# THAT_1646_Breakout.net
KiCad netlist of a schematic drawn in EAGLE
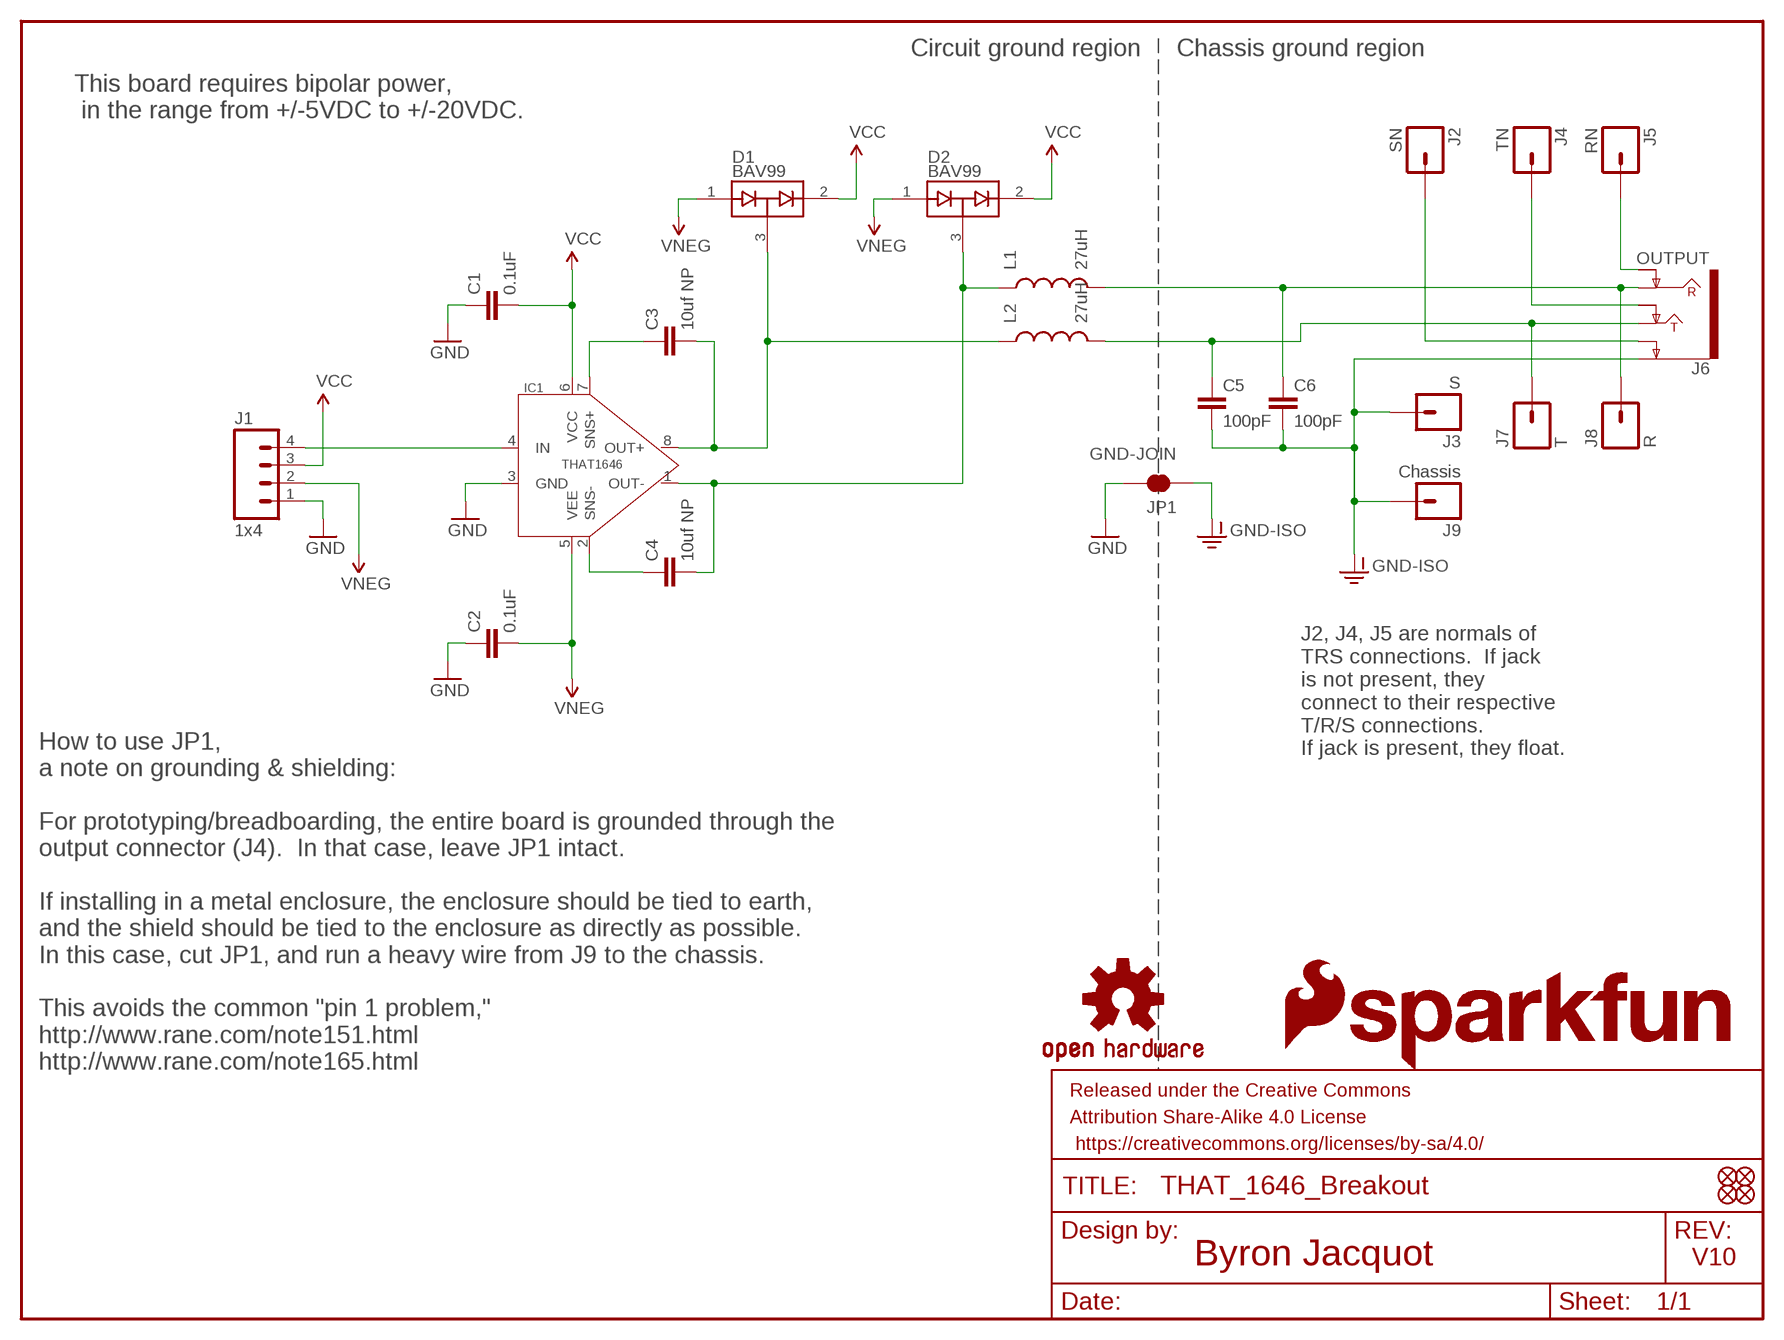
[diagram p0: schematic, sheet 1]

(export (version "E")
  (design (tool "Eeschema 10.0.6"))
  (components
    (comp (ref "C1")
      (value "0.1uF")
      (footprint "eagle-import:0603-CAP")
      (libsource (lib "eagle-import") (part "0.1UF-25V-5%(0603)"))
    )
    (comp (ref "C2")
      (value "0.1uF")
      (footprint "eagle-import:0603-CAP")
      (libsource (lib "eagle-import") (part "0.1UF-25V-5%(0603)"))
    )
    (comp (ref "C3")
      (value "10uf NP")
      (footprint "eagle-import:PANASONIC_D")
      (fields (field (name "MFR") "Panasonic"))
      (libsource (lib "eagle-import") (part "PANA-EEE-1EA100NP"))
    )
    (comp (ref "C4")
      (value "10uf NP")
      (footprint "eagle-import:PANASONIC_D")
      (fields (field (name "MFR") "Panasonic"))
      (libsource (lib "eagle-import") (part "PANA-EEE-1EA100NP"))
    )
    (comp (ref "C5")
      (value "100pF")
      (footprint "eagle-import:0603-CAP")
      (libsource (lib "eagle-import") (part "100PF-50V-5%(0603)"))
    )
    (comp (ref "C6")
      (value "100pF")
      (footprint "eagle-import:0603-CAP")
      (libsource (lib "eagle-import") (part "100PF-50V-5%(0603)"))
    )
    (comp (ref "D1")
      (value "BAV99")
      (footprint "eagle-import:SOT23-3")
      (libsource (lib "eagle-import") (part "BAV99"))
    )
    (comp (ref "D2")
      (value "BAV99")
      (footprint "eagle-import:SOT23-3")
      (libsource (lib "eagle-import") (part "BAV99"))
    )
    (comp (ref "FD1")
      (value "FIDUCIALUFIDUCIAL")
      (footprint "eagle-import:MICRO-FIDUCIAL")
      (libsource (lib "eagle-import") (part "FIDUCIALUFIDUCIAL"))
    )
    (comp (ref "FD2")
      (value "FIDUCIALUFIDUCIAL")
      (footprint "eagle-import:MICRO-FIDUCIAL")
      (libsource (lib "eagle-import") (part "FIDUCIALUFIDUCIAL"))
    )
    (comp (ref "FD3")
      (value "FIDUCIALUFIDUCIAL")
      (footprint "eagle-import:MICRO-FIDUCIAL")
      (libsource (lib "eagle-import") (part "FIDUCIALUFIDUCIAL"))
    )
    (comp (ref "FD4")
      (value "FIDUCIALUFIDUCIAL")
      (footprint "eagle-import:MICRO-FIDUCIAL")
      (libsource (lib "eagle-import") (part "FIDUCIALUFIDUCIAL"))
    )
    (comp (ref "FRAME1")
      (value "FRAME-LETTER")
      (footprint "eagle-import:CREATIVE_COMMONS")
      (libsource (lib "eagle-import") (part "FRAME-LETTER"))
    )
    (comp (ref "IC1")
      (value "THAT1646")
      (footprint "eagle-import:SO08")
      (libsource (lib "eagle-import") (part "THAT1646"))
    )
    (comp (ref "J1")
      (value "1x4")
      (footprint "eagle-import:1X04_NO_SILK_ALL_ROUND")
      (libsource (lib "eagle-import") (part "M04NO_SILK_ALL_ROUND"))
    )
    (comp (ref "J2")
      (value "SN")
      (footprint "eagle-import:1X01_NO_SILK")
      (libsource (lib "eagle-import") (part "M01PTH_NO_SILK_YES_STOP"))
    )
    (comp (ref "J3")
      (value "S")
      (footprint "eagle-import:1X01_NO_SILK")
      (libsource (lib "eagle-import") (part "M01PTH_NO_SILK_YES_STOP"))
    )
    (comp (ref "J4")
      (value "TN")
      (footprint "eagle-import:1X01_NO_SILK")
      (libsource (lib "eagle-import") (part "M01PTH_NO_SILK_YES_STOP"))
    )
    (comp (ref "J5")
      (value "RN")
      (footprint "eagle-import:1X01_NO_SILK")
      (libsource (lib "eagle-import") (part "M01PTH_NO_SILK_YES_STOP"))
    )
    (comp (ref "J6")
      (value "OUTPUT")
      (footprint "eagle-import:AUDIO_JACK_0.25__TRS_PTH_RA")
      (libsource (lib "eagle-import") (part "AUDIO_JACK_TRS_0.25{dblquote}_PTH_RA"))
    )
    (comp (ref "J7")
      (value "T")
      (footprint "eagle-import:1X01_NO_SILK")
      (libsource (lib "eagle-import") (part "M01PTH_NO_SILK_YES_STOP"))
    )
    (comp (ref "J8")
      (value "R")
      (footprint "eagle-import:1X01_NO_SILK")
      (libsource (lib "eagle-import") (part "M01PTH_NO_SILK_YES_STOP"))
    )
    (comp (ref "J9")
      (value "Chassis")
      (footprint "eagle-import:1X01_NO_SILK")
      (libsource (lib "eagle-import") (part "M01PTH_NO_SILK_YES_STOP"))
    )
    (comp (ref "JP1")
      (value "GND-JOIN")
      (footprint "eagle-import:PAD-JUMPER-2-NC_BY_TRACE_YES_SILK")
      (libsource (lib "eagle-import") (part "JUMPER-PAD-2-NC_BY_TRACE"))
    )
    (comp (ref "L1")
      (value "27uH")
      (footprint "eagle-import:0603")
      (libsource (lib "eagle-import") (part "INDUCTOR0603"))
    )
    (comp (ref "L2")
      (value "27uH")
      (footprint "eagle-import:0603")
      (libsource (lib "eagle-import") (part "INDUCTOR0603"))
    )
    (comp (ref "LOGO1")
      (value "OSHW-LOGOS")
      (footprint "eagle-import:OSHW-LOGO-S")
      (libsource (lib "eagle-import") (part "OSHW-LOGOS"))
    )
    (comp (ref "LOGO2")
      (value "OSHW-LOGOS")
      (footprint "eagle-import:OSHW-LOGO-S")
      (libsource (lib "eagle-import") (part "OSHW-LOGOS"))
    )
    (comp (ref "LOGO4")
      (value "SFE_LOGO_FLAME.2_INCH")
      (footprint "eagle-import:SFE_LOGO_FLAME_.2")
      (libsource (lib "eagle-import") (part "SFE_LOGO_FLAME.2_INCH"))
    )
    (comp (ref "LOGO5")
      (value "SFE_LOGO_NAME.1_INCH")
      (footprint "eagle-import:SFE_LOGO_NAME_.1")
      (libsource (lib "eagle-import") (part "SFE_LOGO_NAME.1_INCH"))
    )
  )
  (nets
    (net (code "1") (name "GND") (class "Default")
      (node (ref "C1") (pin "1") (pinfunction "1_1") (pintype "passive"))
      (node (ref "C2") (pin "1") (pinfunction "1_1") (pintype "passive"))
      (node (ref "IC1") (pin "3") (pinfunction "GND_3") (pintype "bidirectional"))
      (node (ref "J1") (pin "1") (pinfunction "1_1") (pintype "passive"))
      (node (ref "JP1") (pin "2") (pinfunction "2_2") (pintype "passive"))
    )
    (net (code "2") (name "GND-ISO") (class "Default")
      (node (ref "C5") (pin "2") (pinfunction "2_2") (pintype "passive"))
      (node (ref "C6") (pin "2") (pinfunction "2_2") (pintype "passive"))
      (node (ref "J3") (pin "1") (pinfunction "1_1") (pintype "passive"))
      (node (ref "J6") (pin "SLEEVE") (pinfunction "EARTH_SLEEVE") (pintype "bidirectional"))
      (node (ref "J9") (pin "1") (pinfunction "1_1") (pintype "passive"))
      (node (ref "JP1") (pin "1") (pinfunction "1_1") (pintype "passive"))
    )
    (net (code "3") (name "Net-(C3-1)") (class "Default")
      (node (ref "C3") (pin "+") (pinfunction "1_+") (pintype "passive"))
      (node (ref "IC1") (pin "7") (pinfunction "SNS+_7") (pintype "bidirectional"))
    )
    (net (code "4") (name "Net-(C3-2)") (class "Default")
      (node (ref "C3") (pin "-") (pinfunction "2_-") (pintype "passive"))
      (node (ref "D1") (pin "3") (pinfunction "COM_3") (pintype "bidirectional"))
      (node (ref "IC1") (pin "8") (pinfunction "OUT+_8") (pintype "bidirectional"))
      (node (ref "L2") (pin "1") (pinfunction "1_1") (pintype "passive"))
    )
    (net (code "5") (name "Net-(C4-1)") (class "Default")
      (node (ref "C4") (pin "+") (pinfunction "1_+") (pintype "passive"))
      (node (ref "IC1") (pin "2") (pinfunction "SNS-_2") (pintype "bidirectional"))
    )
    (net (code "6") (name "Net-(C4-2)") (class "Default")
      (node (ref "C4") (pin "-") (pinfunction "2_-") (pintype "passive"))
      (node (ref "D2") (pin "3") (pinfunction "COM_3") (pintype "bidirectional"))
      (node (ref "IC1") (pin "1") (pinfunction "OUT-_1") (pintype "bidirectional"))
      (node (ref "L1") (pin "1") (pinfunction "1_1") (pintype "passive"))
    )
    (net (code "7") (name "Net-(C5-Pad1)") (class "Default")
      (node (ref "C5") (pin "1") (pinfunction "1_1") (pintype "passive"))
      (node (ref "J6") (pin "TIP") (pinfunction "TIP_TIP") (pintype "bidirectional"))
      (node (ref "J7") (pin "1") (pinfunction "1_1") (pintype "passive"))
      (node (ref "L2") (pin "2") (pinfunction "2_2") (pintype "passive"))
    )
    (net (code "8") (name "Net-(C6-Pad1)") (class "Default")
      (node (ref "C6") (pin "1") (pinfunction "1_1") (pintype "passive"))
      (node (ref "J6") (pin "RING") (pinfunction "RING_RING") (pintype "bidirectional"))
      (node (ref "J8") (pin "1") (pinfunction "1_1") (pintype "passive"))
      (node (ref "L1") (pin "2") (pinfunction "2_2") (pintype "passive"))
    )
    (net (code "9") (name "Net-(IC1-IN)") (class "Default")
      (node (ref "IC1") (pin "4") (pinfunction "IN_4") (pintype "bidirectional"))
      (node (ref "J1") (pin "4") (pinfunction "4_4") (pintype "passive"))
    )
    (net (code "10") (name "Net-(J4-Pad1)") (class "Default")
      (node (ref "J4") (pin "1") (pinfunction "1_1") (pintype "passive"))
      (node (ref "J6") (pin "TIP-NORM") (pinfunction "TIP-NORM_TIP-NORM") (pintype "bidirectional"))
    )
    (net (code "11") (name "Net-(J5-Pad1)") (class "Default")
      (node (ref "J5") (pin "1") (pinfunction "1_1") (pintype "passive"))
      (node (ref "J6") (pin "RING-NORM") (pinfunction "RING-NORM_RING-NORM") (pintype "bidirectional"))
    )
    (net (code "12") (name "Net-(J6-EARTH-NORM)") (class "Default")
      (node (ref "J2") (pin "1") (pinfunction "1_1") (pintype "passive"))
      (node (ref "J6") (pin "SLEEVE-NORM") (pinfunction "EARTH-NORM_SLEEVE-NORM") (pintype "bidirectional"))
    )
    (net (code "13") (name "VCC") (class "Default")
      (node (ref "C1") (pin "2") (pinfunction "2_2") (pintype "passive"))
      (node (ref "D1") (pin "2") (pinfunction "C2_2") (pintype "bidirectional"))
      (node (ref "D2") (pin "2") (pinfunction "C2_2") (pintype "bidirectional"))
      (node (ref "IC1") (pin "6") (pinfunction "VCC_6") (pintype "bidirectional"))
      (node (ref "J1") (pin "3") (pinfunction "3_3") (pintype "passive"))
    )
    (net (code "14") (name "VNEG") (class "Default")
      (node (ref "C2") (pin "2") (pinfunction "2_2") (pintype "passive"))
      (node (ref "D1") (pin "1") (pinfunction "A1_1") (pintype "bidirectional"))
      (node (ref "D2") (pin "1") (pinfunction "A1_1") (pintype "bidirectional"))
      (node (ref "IC1") (pin "5") (pinfunction "VEE_5") (pintype "bidirectional"))
      (node (ref "J1") (pin "2") (pinfunction "2_2") (pintype "passive"))
    )
  )
)
